# zb_button.net
KiCad netlist of a schematic drawn in Altium Designer
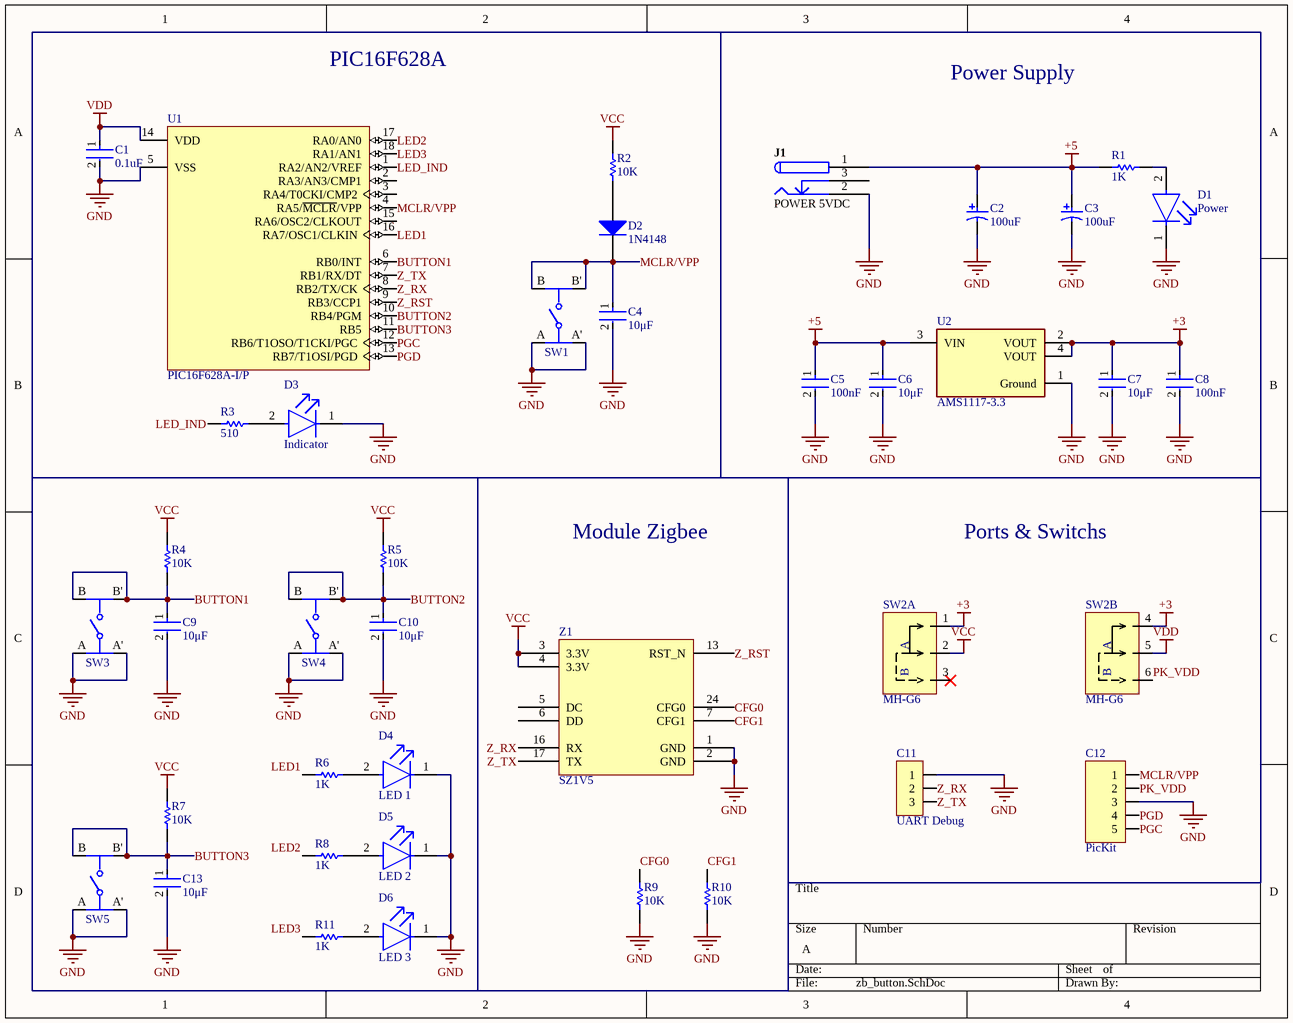
[diagram p0: zb_button.SchDoc]

(export (version "E")
  (design (tool "Eeschema 10.0.6"))
  (components
    (comp (ref "C1")
      (value "0.1uF")
      (footprint "FP-0603-L_1_6_0_15-W_0_81-MFG")
      (description "General Purpose Ceramic Capacitor, 0603, 100nF, 10%, X7R, 15%, 50V")
      (fields (field (name "TOLERANCE") "10%") (field (name "VOLTAGE") "50V"))
      (libsource (lib "Altium Content Vault") (part "02cd4be3c70576c341d710602a673aa"))
    )
    (comp (ref "C2")
      (value "100uF")
      (footprint "PNSC-FK-V-D8_V")
      (fields (field (name "MANUFACTURER") "Panasonic"))
      (libsource (lib "Altium Content Vault") (part "CAP-P-2"))
    )
    (comp (ref "C3")
      (value "100uF")
      (footprint "PNSC-FK-V-D8_V")
      (fields (field (name "MANUFACTURER") "Panasonic"))
      (libsource (lib "Altium Content Vault") (part "CAP-P-2"))
    )
    (comp (ref "C4")
      (value "10μF")
      (footprint "FP-0603-L_1_6_0_15-W_0_81-IPC_A")
      (description "General Purpose Ceramic Capacitor, 0603, 100nF, 10%, X7R, 15%, 50V")
      (fields (field (name "TOLERANCE") "10%") (field (name "VOLTAGE") "50V"))
      (libsource (lib "Altium Content Vault") (part "02cd4be3c70576c341d710602a673aa"))
    )
    (comp (ref "C5")
      (value "100nF")
      (footprint "FP-0603-L_1_6_0_15-W_0_81-IPC_A")
      (description "General Purpose Ceramic Capacitor, 0603, 100nF, 10%, X7R, 15%, 50V")
      (fields (field (name "TOLERANCE") "10%") (field (name "VOLTAGE") "50V"))
      (libsource (lib "Altium Content Vault") (part "02cd4be3c70576c341d710602a673aa"))
    )
    (comp (ref "C6")
      (value "10μF")
      (footprint "FP-0603-L_1_6_0_15-W_0_81-IPC_A")
      (description "General Purpose Ceramic Capacitor, 0603, 100nF, 10%, X7R, 15%, 50V")
      (fields (field (name "TOLERANCE") "10%") (field (name "VOLTAGE") "50V"))
      (libsource (lib "Altium Content Vault") (part "02cd4be3c70576c341d710602a673aa"))
    )
    (comp (ref "C7")
      (value "10μF")
      (footprint "FP-0603-L_1_6_0_15-W_0_81-IPC_A")
      (description "General Purpose Ceramic Capacitor, 0603, 100nF, 10%, X7R, 15%, 50V")
      (fields (field (name "TOLERANCE") "10%") (field (name "VOLTAGE") "50V"))
      (libsource (lib "Altium Content Vault") (part "02cd4be3c70576c341d710602a673aa"))
    )
    (comp (ref "C8")
      (value "100nF")
      (footprint "FP-0603-L_1_6_0_15-W_0_81-IPC_A")
      (description "General Purpose Ceramic Capacitor, 0603, 100nF, 10%, X7R, 15%, 50V")
      (fields (field (name "TOLERANCE") "10%") (field (name "VOLTAGE") "50V"))
      (libsource (lib "Altium Content Vault") (part "02cd4be3c70576c341d710602a673aa"))
    )
    (comp (ref "C9")
      (value "10μF")
      (footprint "FP-0603-L_1_6_0_15-W_0_81-IPC_A")
      (description "General Purpose Ceramic Capacitor, 0603, 100nF, 10%, X7R, 15%, 50V")
      (fields (field (name "TOLERANCE") "10%") (field (name "VOLTAGE") "50V"))
      (libsource (lib "Altium Content Vault") (part "02cd4be3c70576c341d710602a673aa"))
    )
    (comp (ref "C10")
      (value "10μF")
      (footprint "FP-0603-L_1_6_0_15-W_0_81-IPC_A")
      (description "General Purpose Ceramic Capacitor, 0603, 100nF, 10%, X7R, 15%, 50V")
      (fields (field (name "TOLERANCE") "10%") (field (name "VOLTAGE") "50V"))
      (libsource (lib "Altium Content Vault") (part "02cd4be3c70576c341d710602a673aa"))
    )
    (comp (ref "C11")
      (value "UART Debug")
      (footprint "JP3-D1C")
      (description "WR-PHD 2.54 mm Angled Socket Header")
      (fields
        (field (name "MANUFACTURER") "Würth Elektronik eiSos GmbH")
        (field (name "PARTNO") "613003143121")
        (field (name "CREATED BY") "Karrer Zheng")
      )
      (libsource (lib "TechMT.VN_Lib_Project v2") (part "JP3"))
    )
    (comp (ref "C12")
      (value "PicKit")
      (footprint "JP5-D1C")
      (description "WR-PHD 2.54 mm Angled Socket Header")
      (fields
        (field (name "MANUFACTURER") "Würth Elektronik eiSos GmbH")
        (field (name "PARTNO") "613005143121")
        (field (name "CREATED BY") "Karrer Zheng")
      )
      (libsource (lib "TechMT.VN_Lib_Project v2") (part "JP5"))
    )
    (comp (ref "C13")
      (value "10μF")
      (footprint "FP-0603-L_1_6_0_15-W_0_81-IPC_A")
      (description "General Purpose Ceramic Capacitor, 0603, 100nF, 10%, X7R, 15%, 50V")
      (fields (field (name "TOLERANCE") "10%") (field (name "VOLTAGE") "50V"))
      (libsource (lib "Altium Content Vault") (part "02cd4be3c70576c341d710602a673aa"))
    )
    (comp (ref "D1")
      (value "Power")
      (footprint "FP-HLMP-4700-MFG")
      (description "LED RED DIFFUSED T-1 3/4 T/H")
      (fields
        (field (name "OCTOPART") "https://octopart.com/hlmp-4700-broadcom-71130526")
        (field (name "MANUFACTURER") "Broadcom")
      )
      (libsource (lib "Altium Content Vault") (part "8706943c75ba83719d021d2fdc84c58"))
    )
    (comp (ref "D2")
      (value "1N4148")
      (footprint "NXP-SOD27-2_V")
      (description "High-speed Diode, 100 V, 450 mA, 2-Pin SOD27, RoHS")
      (fields (field (name "MANUFACTURER") "NXP Semiconductors"))
      (libsource (lib "Altium Content Vault") (part "NXP-A1K2-2"))
    )
    (comp (ref "D3")
      (value "Indicator")
      (footprint "FP-HLMP-4700-MFG")
      (description "LED RED DIFFUSED T-1 3/4 T/H")
      (fields
        (field (name "OCTOPART") "https://octopart.com/hlmp-4700-broadcom-71130526")
        (field (name "MANUFACTURER") "Broadcom")
      )
      (libsource (lib "Altium Content Vault") (part "8706943c75ba83719d021d2fdc84c58"))
    )
    (comp (ref "D4")
      (value "LED 1")
      (footprint "FP-HLMP-4700-MFG")
      (description "LED RED DIFFUSED T-1 3/4 T/H")
      (fields
        (field (name "OCTOPART") "https://octopart.com/hlmp-4700-broadcom-71130526")
        (field (name "MANUFACTURER") "Broadcom")
      )
      (libsource (lib "Altium Content Vault") (part "8706943c75ba83719d021d2fdc84c58"))
    )
    (comp (ref "D5")
      (value "LED 2")
      (footprint "FP-HLMP-4700-MFG")
      (description "LED RED DIFFUSED T-1 3/4 T/H")
      (fields
        (field (name "OCTOPART") "https://octopart.com/hlmp-4700-broadcom-71130526")
        (field (name "MANUFACTURER") "Broadcom")
      )
      (libsource (lib "Altium Content Vault") (part "8706943c75ba83719d021d2fdc84c58"))
    )
    (comp (ref "D6")
      (value "LED 3")
      (footprint "FP-HLMP-4700-MFG")
      (description "LED RED DIFFUSED T-1 3/4 T/H")
      (fields
        (field (name "OCTOPART") "https://octopart.com/hlmp-4700-broadcom-71130526")
        (field (name "MANUFACTURER") "Broadcom")
      )
      (libsource (lib "Altium Content Vault") (part "8706943c75ba83719d021d2fdc84c58"))
    )
    (comp (ref "J1")
      (value "POWER 5VDC")
      (footprint "KYCN-KLDX-0202-B_V")
      (description "3 Conductor Power Jack, 2 break 2 aux contacts")
      (fields (field (name "PARTNUMBER") "KLDX-0202-B"))
      (libsource (lib "Altium Content Vault") (part "KYCN-KLDX-0202-B-3"))
    )
    (comp (ref "R1")
      (value "1K")
      (footprint "RESC1609X55X30ML15T15")
      (description "Chip Resistor, 10 KOhm, +/- 1%, 0.1 W, -55 to 155 degC, 0603 (1608 Metric), RoHS, Tape and Reel")
      (fields (field (name "TOLERANCE") "1%") (field (name "MANUFACTURER") "Panasonic"))
      (libsource (lib "Altium Content Vault") (part "RES-2"))
    )
    (comp (ref "R2")
      (value "10K")
      (footprint "RESC1609X55X30ML15T15")
      (description "Chip Resistor, 10 KOhm, +/- 1%, 0.1 W, -55 to 155 degC, 0603 (1608 Metric), RoHS, Tape and Reel")
      (fields (field (name "TOLERANCE") "1%") (field (name "MANUFACTURER") "Panasonic"))
      (libsource (lib "Altium Content Vault") (part "RES-2"))
    )
    (comp (ref "R3")
      (value "510")
      (footprint "RESC1609X55X30ML15T15")
      (description "Chip Resistor, 10 KOhm, +/- 1%, 0.1 W, -55 to 155 degC, 0603 (1608 Metric), RoHS, Tape and Reel")
      (fields (field (name "TOLERANCE") "1%") (field (name "MANUFACTURER") "Panasonic"))
      (libsource (lib "Altium Content Vault") (part "RES-2"))
    )
    (comp (ref "R4")
      (value "10K")
      (footprint "RESC1609X55X30ML15T15")
      (description "Chip Resistor, 10 KOhm, +/- 1%, 0.1 W, -55 to 155 degC, 0603 (1608 Metric), RoHS, Tape and Reel")
      (fields (field (name "TOLERANCE") "1%") (field (name "MANUFACTURER") "Panasonic"))
      (libsource (lib "Altium Content Vault") (part "RES-2"))
    )
    (comp (ref "R5")
      (value "10K")
      (footprint "RESC1609X55X30ML15T15")
      (description "Chip Resistor, 10 KOhm, +/- 1%, 0.1 W, -55 to 155 degC, 0603 (1608 Metric), RoHS, Tape and Reel")
      (fields (field (name "TOLERANCE") "1%") (field (name "MANUFACTURER") "Panasonic"))
      (libsource (lib "Altium Content Vault") (part "RES-2"))
    )
    (comp (ref "R6")
      (value "1K")
      (footprint "RESC1609X55X30ML15T15")
      (description "Chip Resistor, 10 KOhm, +/- 1%, 0.1 W, -55 to 155 degC, 0603 (1608 Metric), RoHS, Tape and Reel")
      (fields (field (name "TOLERANCE") "1%") (field (name "MANUFACTURER") "Panasonic"))
      (libsource (lib "Altium Content Vault") (part "RES-2"))
    )
    (comp (ref "R7")
      (value "10K")
      (footprint "RESC1609X55X30ML15T15")
      (description "Chip Resistor, 10 KOhm, +/- 1%, 0.1 W, -55 to 155 degC, 0603 (1608 Metric), RoHS, Tape and Reel")
      (fields (field (name "TOLERANCE") "1%") (field (name "MANUFACTURER") "Panasonic"))
      (libsource (lib "Altium Content Vault") (part "RES-2"))
    )
    (comp (ref "R8")
      (value "1K")
      (footprint "RESC1609X55X30ML15T15")
      (description "Chip Resistor, 10 KOhm, +/- 1%, 0.1 W, -55 to 155 degC, 0603 (1608 Metric), RoHS, Tape and Reel")
      (fields (field (name "TOLERANCE") "1%") (field (name "MANUFACTURER") "Panasonic"))
      (libsource (lib "Altium Content Vault") (part "RES-2"))
    )
    (comp (ref "R9")
      (value "10K")
      (footprint "RESC1609X55X30ML15T15")
      (description "Chip Resistor, 10 KOhm, +/- 1%, 0.1 W, -55 to 155 degC, 0603 (1608 Metric), RoHS, Tape and Reel")
      (fields (field (name "TOLERANCE") "1%") (field (name "MANUFACTURER") "Panasonic"))
      (libsource (lib "Altium Content Vault") (part "RES-2"))
    )
    (comp (ref "R10")
      (value "10K")
      (footprint "RESC1609X55X30ML15T15")
      (description "Chip Resistor, 10 KOhm, +/- 1%, 0.1 W, -55 to 155 degC, 0603 (1608 Metric), RoHS, Tape and Reel")
      (fields (field (name "TOLERANCE") "1%") (field (name "MANUFACTURER") "Panasonic"))
      (libsource (lib "Altium Content Vault") (part "RES-2"))
    )
    (comp (ref "R11")
      (value "1K")
      (footprint "RESC1609X55X30ML15T15")
      (description "Chip Resistor, 10 KOhm, +/- 1%, 0.1 W, -55 to 155 degC, 0603 (1608 Metric), RoHS, Tape and Reel")
      (fields (field (name "TOLERANCE") "1%") (field (name "MANUFACTURER") "Panasonic"))
      (libsource (lib "Altium Content Vault") (part "RES-2"))
    )
    (comp (ref "SW1")
      (value "RESET")
      (footprint "FP-EVQ-PAG05R-MFG")
      (description "SWITCH TACTILE SPST-NO 0.02A 15V")
      (libsource (lib "Altium Content Vault") (part "841f23923f71b23f3ea0ab5dfb78dcc"))
    )
    (comp (ref "SW2")
      (value "MH-G6")
      (footprint "MH-G6")
      (description "6-pin switch MH-G6 2.54mm")
      (libsource (lib "MH-G6") (part "MH-G6"))
    )
    (comp (ref "SW3")
      (value "BUTTON 1")
      (footprint "FP-EVQ-PAG05R-MFG")
      (description "SWITCH TACTILE SPST-NO 0.02A 15V")
      (libsource (lib "Altium Content Vault") (part "841f23923f71b23f3ea0ab5dfb78dcc"))
    )
    (comp (ref "SW4")
      (value "BUTTON 2")
      (footprint "FP-EVQ-PAG05R-MFG")
      (description "SWITCH TACTILE SPST-NO 0.02A 15V")
      (libsource (lib "Altium Content Vault") (part "841f23923f71b23f3ea0ab5dfb78dcc"))
    )
    (comp (ref "SW5")
      (value "BUTTON 3")
      (footprint "FP-EVQ-PAG05R-MFG")
      (description "SWITCH TACTILE SPST-NO 0.02A 15V")
      (libsource (lib "Altium Content Vault") (part "841f23923f71b23f3ea0ab5dfb78dcc"))
    )
    (comp (ref "U1")
      (value "PIC16F628A-I/P")
      (footprint "PDIP300-P18")
      (libsource (lib "Altium Content Vault") (part "MC-8B-16F627A-IL18"))
    )
    (comp (ref "U2")
      (value "AMS1117-3.3")
      (footprint "FP-AMS1117-IPC_A")
      (description "LDO Voltage Regulators 1A, 3.3V")
      (fields
        (field (name "OCTOPART") "https://octopart.com/ams1117-3.3-advanced+monolithic+systems-25899300")
        (field (name "MANUFACTURER") "Advanced Monolithic Systems")
      )
      (libsource (lib "Altium Content Vault") (part "8bdbb5f8e77002000e30dd2845d0354"))
    )
    (comp (ref "Z1")
      (value "SZ1V5")
      (footprint "SZ1V5 PINOUT MODULE")
      (libsource (lib "SZ1V5") (part "SZ1V5_Alt"))
    )
  )
  (nets
    (net (code "1") (name "+3") (class "Default")
      (node (ref "C7") (pin "1") (pinfunction "1_1") (pintype "passive"))
      (node (ref "C8") (pin "1") (pinfunction "1_1") (pintype "passive"))
      (node (ref "SW2") (pin "1") (pinfunction "A_1") (pintype "passive"))
      (node (ref "SW2") (pin "4") (pinfunction "A_4") (pintype "passive"))
      (node (ref "U2") (pin "2") (pinfunction "VOUT_2") (pintype "passive"))
      (node (ref "U2") (pin "4") (pinfunction "VOUT_4") (pintype "passive"))
    )
    (net (code "2") (name "+5") (class "Default")
      (node (ref "C2") (pin "1") (pinfunction "1_1") (pintype "passive"))
      (node (ref "C3") (pin "1") (pinfunction "1_1") (pintype "passive"))
      (node (ref "C5") (pin "1") (pinfunction "1_1") (pintype "passive"))
      (node (ref "C6") (pin "1") (pinfunction "1_1") (pintype "passive"))
      (node (ref "J1") (pin "1") (pintype "power_in"))
      (node (ref "R1") (pin "2") (pinfunction "2_2") (pintype "passive"))
      (node (ref "U2") (pin "3") (pinfunction "VIN_3") (pintype "power_in"))
    )
    (net (code "3") (name "/BUTTON1") (class "Default")
      (node (ref "C9") (pin "1") (pinfunction "1_1") (pintype "passive"))
      (node (ref "R4") (pin "1") (pinfunction "1_1") (pintype "passive"))
      (node (ref "SW3") (pin "B") (pinfunction "B_B") (pintype "passive"))
      (node (ref "SW3") (pin "B'") (pinfunction "B'_B'") (pintype "passive"))
      (node (ref "U1") (pin "6") (pinfunction "RB0/INT_6") (pintype "bidirectional"))
    )
    (net (code "4") (name "/BUTTON2") (class "Default")
      (node (ref "C10") (pin "1") (pinfunction "1_1") (pintype "passive"))
      (node (ref "R5") (pin "1") (pinfunction "1_1") (pintype "passive"))
      (node (ref "SW4") (pin "B") (pinfunction "B_B") (pintype "passive"))
      (node (ref "SW4") (pin "B'") (pinfunction "B'_B'") (pintype "passive"))
      (node (ref "U1") (pin "10") (pinfunction "RB4/PGM_10") (pintype "bidirectional"))
    )
    (net (code "5") (name "/BUTTON3") (class "Default")
      (node (ref "C13") (pin "1") (pinfunction "1_1") (pintype "passive"))
      (node (ref "R7") (pin "1") (pinfunction "1_1") (pintype "passive"))
      (node (ref "SW5") (pin "B") (pinfunction "B_B") (pintype "passive"))
      (node (ref "SW5") (pin "B'") (pinfunction "B'_B'") (pintype "passive"))
      (node (ref "U1") (pin "11") (pinfunction "RB5_11") (pintype "bidirectional"))
    )
    (net (code "6") (name "/CFG0") (class "Default")
      (node (ref "R9") (pin "2") (pinfunction "2_2") (pintype "passive"))
      (node (ref "Z1") (pin "24") (pinfunction "CFG0_24") (pintype "passive"))
    )
    (net (code "7") (name "/CFG1") (class "Default")
      (node (ref "R10") (pin "2") (pinfunction "2_2") (pintype "passive"))
      (node (ref "Z1") (pin "7") (pinfunction "CFG1_7") (pintype "passive"))
    )
    (net (code "8") (name "/LED1") (class "Default")
      (node (ref "R6") (pin "1") (pinfunction "1_1") (pintype "passive"))
      (node (ref "U1") (pin "16") (pinfunction "RA7/OSC1/CLKIN_16") (pintype "bidirectional"))
    )
    (net (code "9") (name "/LED2") (class "Default")
      (node (ref "R8") (pin "1") (pinfunction "1_1") (pintype "passive"))
      (node (ref "U1") (pin "17") (pinfunction "RA0/AN0_17") (pintype "bidirectional"))
    )
    (net (code "10") (name "/LED3") (class "Default")
      (node (ref "R11") (pin "1") (pinfunction "1_1") (pintype "passive"))
      (node (ref "U1") (pin "18") (pinfunction "RA1/AN1_18") (pintype "bidirectional"))
    )
    (net (code "11") (name "/LED_IND") (class "Default")
      (node (ref "R3") (pin "2") (pinfunction "2_2") (pintype "passive"))
      (node (ref "U1") (pin "1") (pinfunction "RA2/AN2/VREF_1") (pintype "bidirectional"))
    )
    (net (code "12") (name "/MCLR{slash}VPP") (class "Default")
      (node (ref "C12") (pin "1") (pinfunction "1_1") (pintype "passive"))
      (node (ref "C4") (pin "1") (pinfunction "1_1") (pintype "passive"))
      (node (ref "D2") (pin "2") (pinfunction "K_2") (pintype "passive"))
      (node (ref "SW1") (pin "B") (pinfunction "B_B") (pintype "passive"))
      (node (ref "SW1") (pin "B'") (pinfunction "B'_B'") (pintype "passive"))
      (node (ref "U1") (pin "4") (pinfunction "RA5/~{MCLR}/VPP_4") (pintype "bidirectional"))
    )
    (net (code "13") (name "/PGC") (class "Default")
      (node (ref "C12") (pin "5") (pinfunction "5_5") (pintype "passive"))
      (node (ref "U1") (pin "12") (pinfunction "RB6/T1OSO/T1CKI/PGC_12") (pintype "bidirectional"))
    )
    (net (code "14") (name "/PGD") (class "Default")
      (node (ref "C12") (pin "4") (pinfunction "4_4") (pintype "passive"))
      (node (ref "U1") (pin "13") (pinfunction "RB7/T1OSI/PGD_13") (pintype "bidirectional"))
    )
    (net (code "15") (name "/PK_VDD") (class "Default")
      (node (ref "C12") (pin "2") (pinfunction "2_2") (pintype "passive"))
      (node (ref "SW2") (pin "6") (pinfunction "B_6") (pintype "passive"))
    )
    (net (code "16") (name "/Z_RST") (class "Default")
      (node (ref "U1") (pin "9") (pinfunction "RB3/CCP1_9") (pintype "bidirectional"))
      (node (ref "Z1") (pin "13") (pinfunction "RST_N_13") (pintype "passive"))
    )
    (net (code "17") (name "/Z_RX") (class "Default")
      (node (ref "C11") (pin "2") (pinfunction "2_2") (pintype "passive"))
      (node (ref "U1") (pin "8") (pinfunction "RB2/TX/CK_8") (pintype "bidirectional"))
      (node (ref "Z1") (pin "16") (pinfunction "RX_16") (pintype "passive"))
    )
    (net (code "18") (name "/Z_TX") (class "Default")
      (node (ref "C11") (pin "3") (pinfunction "3_3") (pintype "passive"))
      (node (ref "U1") (pin "7") (pinfunction "RB1/RX/DT_7") (pintype "bidirectional"))
      (node (ref "Z1") (pin "17") (pinfunction "TX_17") (pintype "passive"))
    )
    (net (code "19") (name "GND") (class "Default")
      (node (ref "C1") (pin "2") (pinfunction "2_2") (pintype "passive"))
      (node (ref "C10") (pin "2") (pinfunction "2_2") (pintype "passive"))
      (node (ref "C11") (pin "1") (pinfunction "1_1") (pintype "passive"))
      (node (ref "C12") (pin "3") (pinfunction "3_3") (pintype "passive"))
      (node (ref "C13") (pin "2") (pinfunction "2_2") (pintype "passive"))
      (node (ref "C2") (pin "2") (pinfunction "2_2") (pintype "passive"))
      (node (ref "C3") (pin "2") (pinfunction "2_2") (pintype "passive"))
      (node (ref "C4") (pin "2") (pinfunction "2_2") (pintype "passive"))
      (node (ref "C5") (pin "2") (pinfunction "2_2") (pintype "passive"))
      (node (ref "C6") (pin "2") (pinfunction "2_2") (pintype "passive"))
      (node (ref "C7") (pin "2") (pinfunction "2_2") (pintype "passive"))
      (node (ref "C8") (pin "2") (pinfunction "2_2") (pintype "passive"))
      (node (ref "C9") (pin "2") (pinfunction "2_2") (pintype "passive"))
      (node (ref "D1") (pin "1") (pinfunction "C_1") (pintype "passive"))
      (node (ref "D3") (pin "1") (pinfunction "C_1") (pintype "passive"))
      (node (ref "D4") (pin "1") (pinfunction "C_1") (pintype "passive"))
      (node (ref "D5") (pin "1") (pinfunction "C_1") (pintype "passive"))
      (node (ref "D6") (pin "1") (pinfunction "C_1") (pintype "passive"))
      (node (ref "J1") (pin "2") (pintype "power_in"))
      (node (ref "R10") (pin "1") (pinfunction "1_1") (pintype "passive"))
      (node (ref "R9") (pin "1") (pinfunction "1_1") (pintype "passive"))
      (node (ref "SW1") (pin "A") (pinfunction "A_A") (pintype "passive"))
      (node (ref "SW1") (pin "A'") (pinfunction "A'_A'") (pintype "passive"))
      (node (ref "SW3") (pin "A") (pinfunction "A_A") (pintype "passive"))
      (node (ref "SW3") (pin "A'") (pinfunction "A'_A'") (pintype "passive"))
      (node (ref "SW4") (pin "A") (pinfunction "A_A") (pintype "passive"))
      (node (ref "SW4") (pin "A'") (pinfunction "A'_A'") (pintype "passive"))
      (node (ref "SW5") (pin "A") (pinfunction "A_A") (pintype "passive"))
      (node (ref "SW5") (pin "A'") (pinfunction "A'_A'") (pintype "passive"))
      (node (ref "U1") (pin "5") (pinfunction "VSS_5") (pintype "power_in"))
      (node (ref "U2") (pin "1") (pinfunction "Ground_1") (pintype "power_in"))
      (node (ref "Z1") (pin "1") (pinfunction "GND_1") (pintype "passive"))
      (node (ref "Z1") (pin "2") (pinfunction "GND_2") (pintype "passive"))
    )
    (net (code "20") (name "Net-(D1-A)") (class "Default")
      (node (ref "D1") (pin "2") (pinfunction "A_2") (pintype "passive"))
      (node (ref "R1") (pin "1") (pinfunction "1_1") (pintype "passive"))
    )
    (net (code "21") (name "Net-(D2-A)") (class "Default")
      (node (ref "D2") (pin "1") (pinfunction "A_1") (pintype "passive"))
      (node (ref "R2") (pin "1") (pinfunction "1_1") (pintype "passive"))
    )
    (net (code "22") (name "Net-(D3-A)") (class "Default")
      (node (ref "D3") (pin "2") (pinfunction "A_2") (pintype "passive"))
      (node (ref "R3") (pin "1") (pinfunction "1_1") (pintype "passive"))
    )
    (net (code "23") (name "Net-(D4-A)") (class "Default")
      (node (ref "D4") (pin "2") (pinfunction "A_2") (pintype "passive"))
      (node (ref "R6") (pin "2") (pinfunction "2_2") (pintype "passive"))
    )
    (net (code "24") (name "Net-(D5-A)") (class "Default")
      (node (ref "D5") (pin "2") (pinfunction "A_2") (pintype "passive"))
      (node (ref "R8") (pin "2") (pinfunction "2_2") (pintype "passive"))
    )
    (net (code "25") (name "Net-(D6-A)") (class "Default")
      (node (ref "D6") (pin "2") (pinfunction "A_2") (pintype "passive"))
      (node (ref "R11") (pin "2") (pinfunction "2_2") (pintype "passive"))
    )
    (net (code "26") (name "VCC") (class "Default")
      (node (ref "R2") (pin "2") (pinfunction "2_2") (pintype "passive"))
      (node (ref "R4") (pin "2") (pinfunction "2_2") (pintype "passive"))
      (node (ref "R5") (pin "2") (pinfunction "2_2") (pintype "passive"))
      (node (ref "R7") (pin "2") (pinfunction "2_2") (pintype "passive"))
      (node (ref "SW2") (pin "2") (pinfunction "COM_2") (pintype "passive"))
      (node (ref "Z1") (pin "3") (pinfunction "3.3V_3") (pintype "passive"))
      (node (ref "Z1") (pin "4") (pinfunction "3.3V_4") (pintype "passive"))
    )
    (net (code "27") (name "VDD") (class "Default")
      (node (ref "C1") (pin "1") (pinfunction "1_1") (pintype "passive"))
      (node (ref "SW2") (pin "5") (pinfunction "COM_5") (pintype "passive"))
      (node (ref "U1") (pin "14") (pinfunction "VDD_14") (pintype "power_in"))
    )
    (net (code "28") (name "unconnected-(J1-Pad3)") (class "Default")
      (node (ref "J1") (pin "3") (pintype "power_in"))
    )
    (net (code "29") (name "unconnected-(SW2A-B-Pad3)") (class "Default")
      (node (ref "SW2") (pin "3") (pinfunction "B_3") (pintype "passive+no_connect"))
    )
    (net (code "30") (name "unconnected-(U1-RA3{slash}AN3{slash}CMP1-Pad2)") (class "Default")
      (node (ref "U1") (pin "2") (pinfunction "RA3/AN3/CMP1_2") (pintype "bidirectional"))
    )
    (net (code "31") (name "unconnected-(U1-RA4{slash}T0CKI{slash}CMP2-Pad3)") (class "Default")
      (node (ref "U1") (pin "3") (pinfunction "RA4/T0CKI/CMP2_3") (pintype "bidirectional"))
    )
    (net (code "32") (name "unconnected-(U1-RA6{slash}OSC2{slash}CLKOUT-Pad15)") (class "Default")
      (node (ref "U1") (pin "15") (pinfunction "RA6/OSC2/CLKOUT_15") (pintype "bidirectional"))
    )
    (net (code "33") (name "unconnected-(Z1-DC-Pad5)") (class "Default")
      (node (ref "Z1") (pin "5") (pinfunction "DC_5") (pintype "passive"))
    )
    (net (code "34") (name "unconnected-(Z1-DD-Pad6)") (class "Default")
      (node (ref "Z1") (pin "6") (pinfunction "DD_6") (pintype "passive"))
    )
  )
)
